# Fri3D_2020_00.net
KiCad netlist of a schematic drawn in Altium Designer
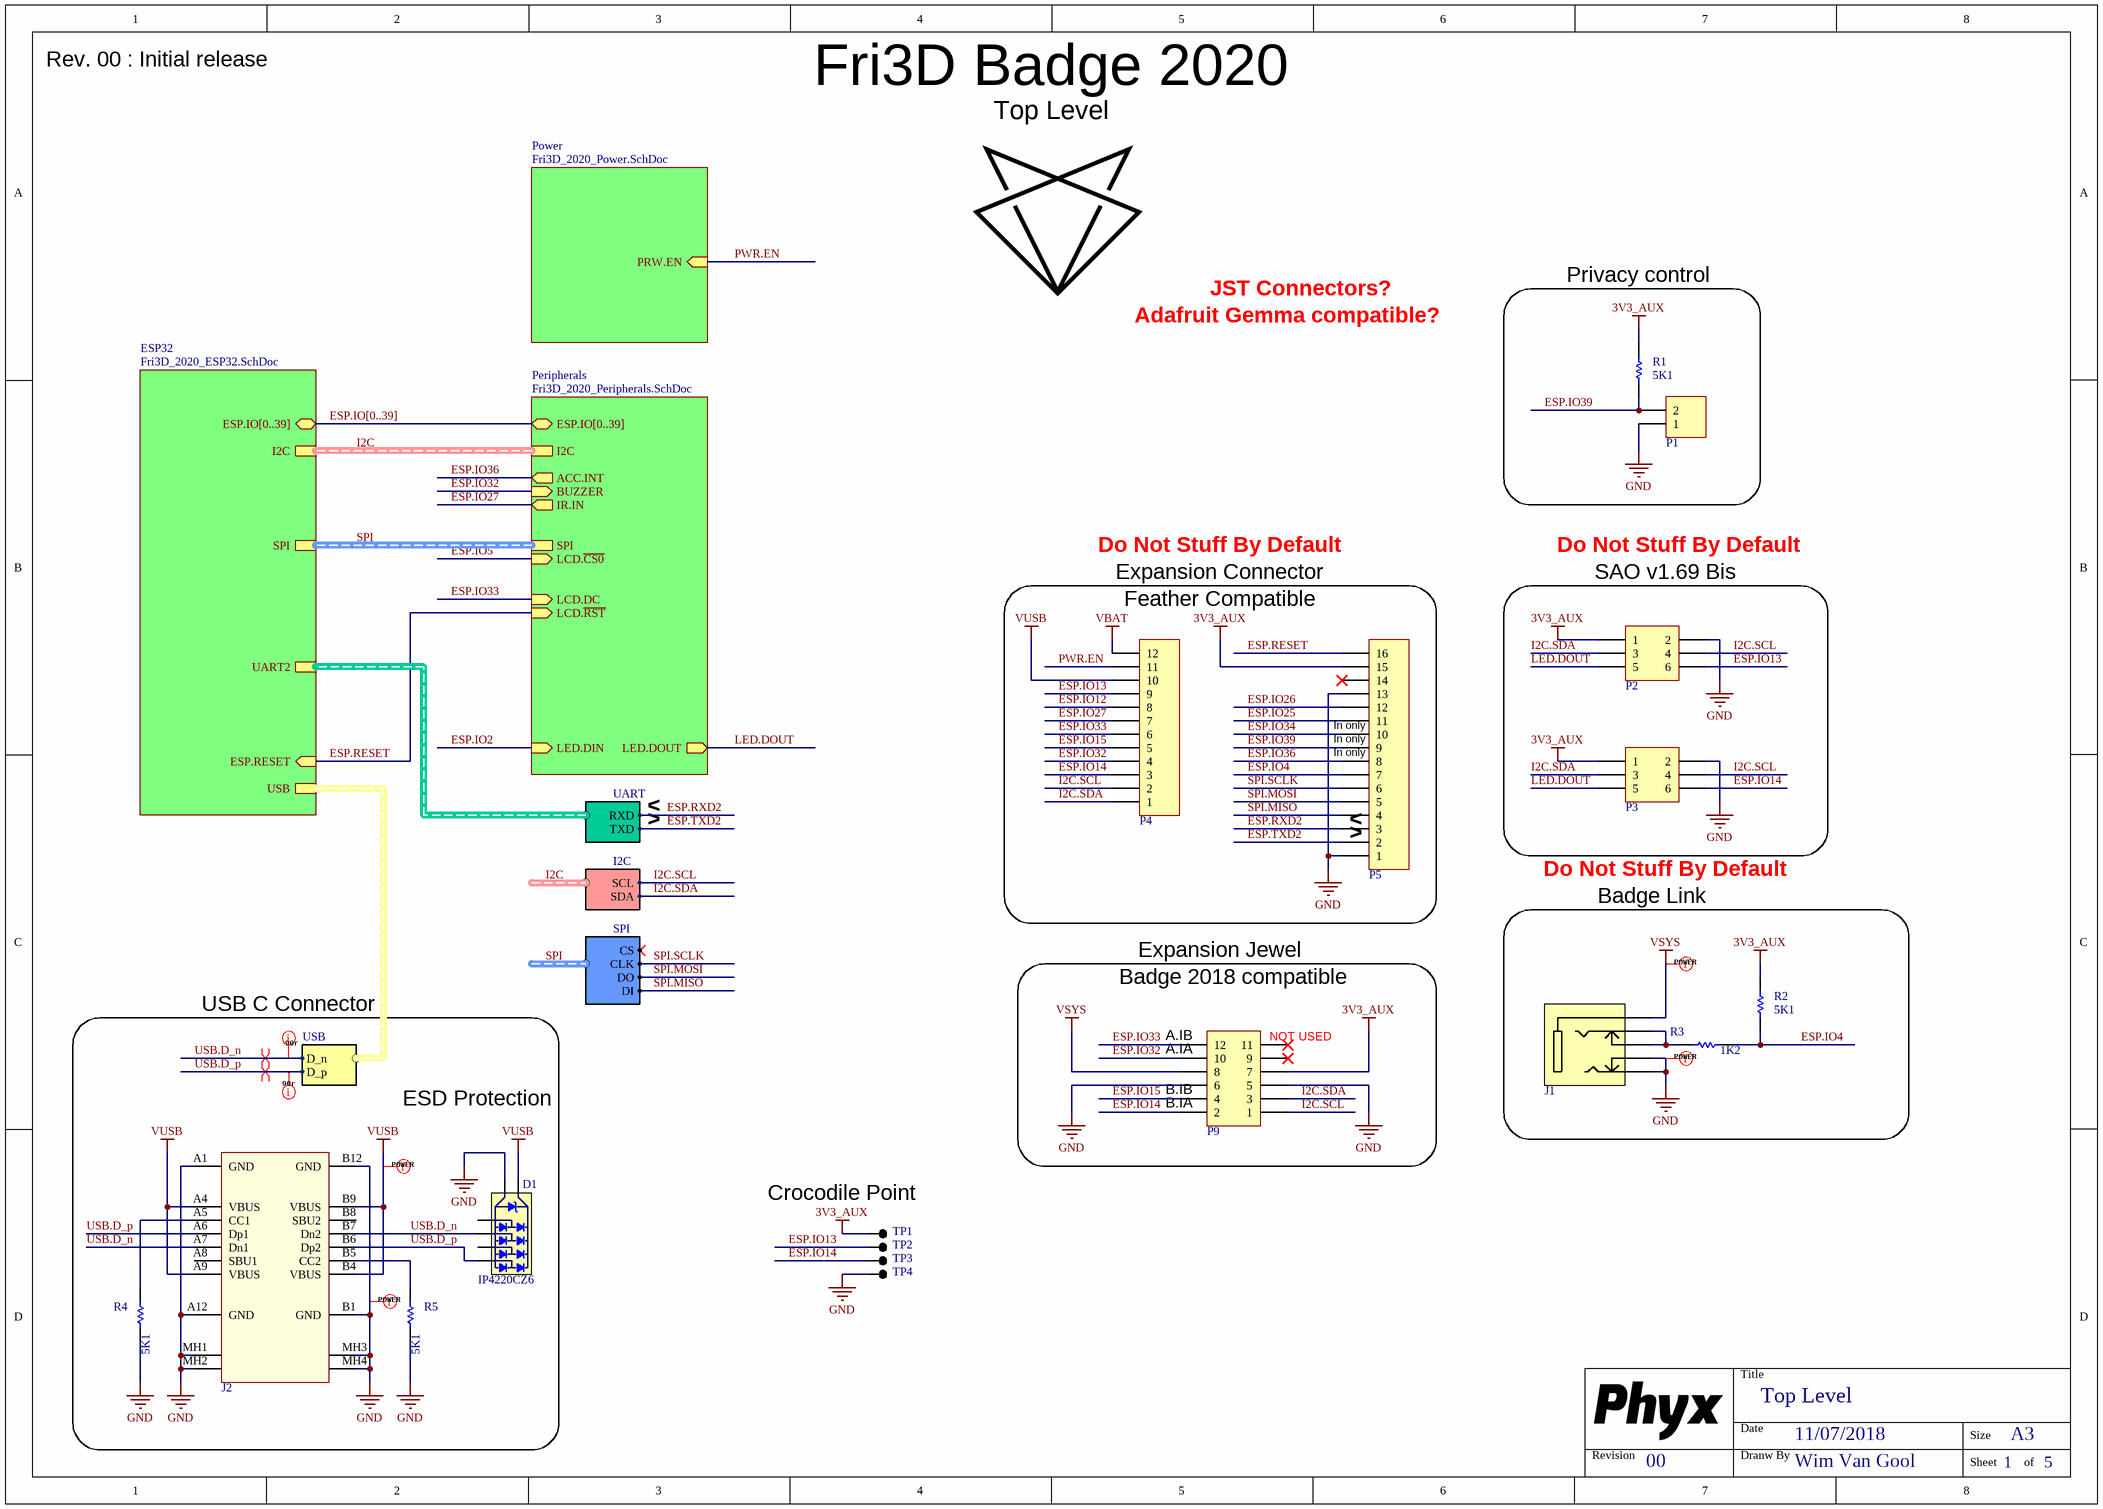
[diagram p0: Fri3D_2020_00.SchDoc]

(export (version "E")
  (design (tool "Eeschema 10.0.6"))
  (components
    (comp (ref "D1")
      (value "IP4220CZ6")
      (footprint "NXP_SOT457")
      (description "=Description")
      (fields (field (name "Comment") "TVS Diode Dual USB"))
      (libsource (lib "Phyx_Components") (part "NXP_IP4220CZ6"))
    )
    (comp (ref "J1")
      (value "3.5mm jack, dual switch, black, 3 contacts")
      (footprint "CUI_SJ1-3525NG")
      (description "=Description")
      (libsource (lib "Phyx_Components") (part "CUI_SJ1-3525NG"))
    )
    (comp (ref "J2")
      (value "USB 2.0 C Reversible Receptacle Horizontal")
      (footprint "HRO_TYPE-C-31-M-12")
      (libsource (lib "Phyx_Components") (part "USB_C_16_4"))
    )
    (comp (ref "P1")
      (value "Easy to solder connection")
      (footprint "SOLDER_SW_V_1MM")
      (libsource (lib "Phyx_Components") (part "Header 2"))
    )
    (comp (ref "P2")
      (value "Receptacle 3x2")
      (footprint "RCPT2X3")
      (libsource (lib "Phyx_Components") (part "Header 3X2"))
    )
    (comp (ref "P3")
      (value "Receptacle 3x2")
      (footprint "RCPT2X3")
      (libsource (lib "Phyx_Components") (part "Header 3X2"))
    )
    (comp (ref "P4")
      (value "Header 12")
      (footprint "HDR1X12")
      (libsource (lib "Phyx_Components") (part "Header 12"))
    )
    (comp (ref "P5")
      (value "Header 16")
      (footprint "HDR1X16")
      (libsource (lib "Phyx_Components") (part "Header 16"))
    )
    (comp (ref "P9")
      (value "Receptacle 6x2 SMD low profile")
      (footprint "WE_610312243021_POST")
      (libsource (lib "Phyx_Components") (part "Header 6X2"))
    )
    (comp (ref "R1")
      (value "5K1")
      (footprint "R0603_N")
      (fields (field (name "Comment") "RESISTOR"))
      (libsource (lib "Phyx_Components") (part "RESISTOR"))
    )
    (comp (ref "R2")
      (value "5K1")
      (footprint "R0603_N")
      (fields (field (name "Comment") "RESISTOR"))
      (libsource (lib "Phyx_Components") (part "RESISTOR"))
    )
    (comp (ref "R3")
      (value "1K2")
      (footprint "R0603_N")
      (fields (field (name "Comment") "RESISTOR"))
      (libsource (lib "Phyx_Components") (part "RESISTOR"))
    )
    (comp (ref "R4")
      (value "5K1")
      (footprint "R0603_N")
      (fields (field (name "Comment") "RESISTOR"))
      (libsource (lib "Phyx_Components") (part "RESISTOR"))
    )
    (comp (ref "R5")
      (value "5K1")
      (footprint "R0603_N")
      (fields (field (name "Comment") "RESISTOR"))
      (libsource (lib "Phyx_Components") (part "RESISTOR"))
    )
    (comp (ref "TP1")
      (value "TEST_PAD")
      (footprint "TP_0.8mm")
      (libsource (lib "Phyx_Components") (part "TEST_PAD"))
    )
    (comp (ref "TP2")
      (value "TEST_PAD")
      (footprint "TP_0.8mm")
      (libsource (lib "Phyx_Components") (part "TEST_PAD"))
    )
    (comp (ref "TP3")
      (value "TEST_PAD")
      (footprint "TP_0.8mm")
      (libsource (lib "Phyx_Components") (part "TEST_PAD"))
    )
    (comp (ref "TP4")
      (value "TEST_PAD")
      (footprint "TP_0.8mm")
      (libsource (lib "Phyx_Components") (part "TEST_PAD"))
    )
  )
  (nets
    (net (code "33") (name "/ESP.IO4") (class "Default")
      (node (ref "P5") (pin "7") (pinfunction "7_7") (pintype "passive"))
      (node (ref "R2") (pin "2") (pinfunction "2_2") (pintype "passive"))
      (node (ref "R3") (pin "1") (pinfunction "1_1") (pintype "passive"))
    )
    (net (code "35") (name "/ESP.IO12") (class "Default")
      (node (ref "P4") (pin "8") (pinfunction "8_8") (pintype "passive"))
    )
    (net (code "36") (name "/ESP.IO13") (class "Default")
      (node (ref "P2") (pin "6") (pinfunction "6_6") (pintype "passive"))
      (node (ref "P4") (pin "9") (pinfunction "9_9") (pintype "passive"))
      (node (ref "TP2") (pin "1") (pinfunction "1_1") (pintype "passive"))
    )
    (net (code "37") (name "/ESP.IO14") (class "Default")
      (node (ref "P3") (pin "6") (pinfunction "6_6") (pintype "passive"))
      (node (ref "P4") (pin "3") (pinfunction "3_3") (pintype "passive"))
      (node (ref "P9") (pin "2") (pinfunction "2_2") (pintype "passive"))
      (node (ref "TP3") (pin "1") (pinfunction "1_1") (pintype "passive"))
    )
    (net (code "38") (name "/ESP.IO15") (class "Default")
      (node (ref "P4") (pin "5") (pinfunction "5_5") (pintype "passive"))
      (node (ref "P9") (pin "4") (pinfunction "4_4") (pintype "passive"))
    )
    (net (code "39") (name "/ESP.IO25") (class "Default")
      (node (ref "P5") (pin "11") (pinfunction "11_11") (pintype "passive"))
    )
    (net (code "40") (name "/ESP.IO26") (class "Default")
      (node (ref "P5") (pin "12") (pinfunction "12_12") (pintype "passive"))
    )
    (net (code "41") (name "/ESP.IO27") (class "Default")
      (node (ref "P4") (pin "7") (pinfunction "7_7") (pintype "passive"))
    )
    (net (code "42") (name "/ESP.IO32") (class "Default")
      (node (ref "P4") (pin "4") (pinfunction "4_4") (pintype "passive"))
      (node (ref "P9") (pin "10") (pinfunction "10_10") (pintype "passive"))
    )
    (net (code "43") (name "/ESP.IO33") (class "Default")
      (node (ref "P4") (pin "6") (pinfunction "6_6") (pintype "passive"))
      (node (ref "P9") (pin "12") (pinfunction "12_12") (pintype "passive"))
    )
    (net (code "44") (name "/ESP.IO34") (class "Default")
      (node (ref "P5") (pin "10") (pinfunction "10_10") (pintype "passive"))
    )
    (net (code "45") (name "/ESP.IO36") (class "Default")
      (node (ref "P5") (pin "8") (pinfunction "8_8") (pintype "passive"))
    )
    (net (code "46") (name "/ESP.IO39") (class "Default")
      (node (ref "P1") (pin "2") (pinfunction "2_2") (pintype "passive"))
      (node (ref "P5") (pin "9") (pinfunction "9_9") (pintype "passive"))
      (node (ref "R1") (pin "2") (pinfunction "2_2") (pintype "passive"))
    )
    (net (code "48") (name "/ESP.RESET") (class "Default")
      (node (ref "P5") (pin "16") (pinfunction "16_16") (pintype "passive"))
    )
    (net (code "49") (name "/ESP.RXD2") (class "Default")
      (node (ref "P5") (pin "3") (pinfunction "3_3") (pintype "passive"))
    )
    (net (code "50") (name "/ESP.TXD2") (class "Default")
      (node (ref "P5") (pin "2") (pinfunction "2_2") (pintype "passive"))
    )
    (net (code "51") (name "/I2C.SCL") (class "Default")
      (node (ref "P2") (pin "4") (pinfunction "4_4") (pintype "passive"))
      (node (ref "P3") (pin "4") (pinfunction "4_4") (pintype "passive"))
      (node (ref "P4") (pin "2") (pinfunction "2_2") (pintype "passive"))
      (node (ref "P9") (pin "1") (pinfunction "1_1") (pintype "passive"))
    )
    (net (code "52") (name "/I2C.SDA") (class "Default")
      (node (ref "P2") (pin "3") (pinfunction "3_3") (pintype "passive"))
      (node (ref "P3") (pin "3") (pinfunction "3_3") (pintype "passive"))
      (node (ref "P4") (pin "1") (pinfunction "1_1") (pintype "passive"))
      (node (ref "P9") (pin "3") (pinfunction "3_3") (pintype "passive"))
    )
    (net (code "54") (name "/LED.DOUT") (class "Default")
      (node (ref "P2") (pin "5") (pinfunction "5_5") (pintype "passive"))
      (node (ref "P3") (pin "5") (pinfunction "5_5") (pintype "passive"))
    )
    (net (code "55") (name "/PWR.EN") (class "Default")
      (node (ref "P4") (pin "11") (pinfunction "11_11") (pintype "passive"))
    )
    (net (code "56") (name "/SPI.MISO") (class "Default")
      (node (ref "P5") (pin "4") (pinfunction "4_4") (pintype "passive"))
    )
    (net (code "57") (name "/SPI.MOSI") (class "Default")
      (node (ref "P5") (pin "5") (pinfunction "5_5") (pintype "passive"))
    )
    (net (code "58") (name "/SPI.SCLK") (class "Default")
      (node (ref "P5") (pin "6") (pinfunction "6_6") (pintype "passive"))
    )
    (net (code "60") (name "/USB.D_n") (class "Default")
      (node (ref "D1") (pin "1") (pinfunction "1_1") (pintype "passive"))
      (node (ref "J2") (pin "A7") (pinfunction "Dn1_A7") (pintype "passive"))
      (node (ref "J2") (pin "B7") (pinfunction "Dn2_B7") (pintype "passive"))
    )
    (net (code "61") (name "/USB.D_p") (class "Default")
      (node (ref "D1") (pin "6") (pinfunction "6_6") (pintype "passive"))
      (node (ref "J2") (pin "A6") (pinfunction "Dp1_A6") (pintype "passive"))
      (node (ref "J2") (pin "B6") (pinfunction "Dp2_B6") (pintype "passive"))
    )
    (net (code "66") (name "3V3_AUX") (class "Default")
      (node (ref "P2") (pin "1") (pinfunction "1_1") (pintype "passive"))
      (node (ref "P3") (pin "1") (pinfunction "1_1") (pintype "passive"))
      (node (ref "P5") (pin "15") (pinfunction "15_15") (pintype "passive"))
      (node (ref "P9") (pin "7") (pinfunction "7_7") (pintype "passive"))
      (node (ref "R1") (pin "1") (pinfunction "1_1") (pintype "passive"))
      (node (ref "R2") (pin "1") (pinfunction "1_1") (pintype "passive"))
      (node (ref "TP1") (pin "1") (pinfunction "1_1") (pintype "passive"))
    )
    (net (code "67") (name "GND") (class "Default")
      (node (ref "D1") (pin "2") (pinfunction "GND_2") (pintype "passive"))
      (node (ref "J1") (pin "2") (pinfunction "Tip_2") (pintype "passive"))
      (node (ref "J1") (pin "4") (pinfunction "4_4") (pintype "passive"))
      (node (ref "J2") (pin "A1") (pinfunction "GND_A1") (pintype "passive"))
      (node (ref "J2") (pin "A12") (pinfunction "GND_A12") (pintype "passive"))
      (node (ref "J2") (pin "B1") (pinfunction "GND_B1") (pintype "passive"))
      (node (ref "J2") (pin "B12") (pinfunction "GND_B12") (pintype "passive"))
      (node (ref "J2") (pin "MH1") (pinfunction "Tab_MH1") (pintype "passive"))
      (node (ref "J2") (pin "MH2") (pinfunction "Tab_MH2") (pintype "passive"))
      (node (ref "J2") (pin "MH3") (pinfunction "Tab_MH3") (pintype "passive"))
      (node (ref "J2") (pin "MH4") (pinfunction "Tab_MH4") (pintype "passive"))
      (node (ref "P1") (pin "1") (pinfunction "1_1") (pintype "passive"))
      (node (ref "P2") (pin "2") (pinfunction "2_2") (pintype "passive"))
      (node (ref "P3") (pin "2") (pinfunction "2_2") (pintype "passive"))
      (node (ref "P5") (pin "1") (pinfunction "1_1") (pintype "passive"))
      (node (ref "P5") (pin "13") (pinfunction "13_13") (pintype "passive"))
      (node (ref "P9") (pin "5") (pinfunction "5_5") (pintype "passive"))
      (node (ref "P9") (pin "6") (pinfunction "6_6") (pintype "passive"))
      (node (ref "R4") (pin "2") (pinfunction "2_2") (pintype "passive"))
      (node (ref "R5") (pin "2") (pinfunction "2_2") (pintype "passive"))
      (node (ref "TP4") (pin "1") (pinfunction "1_1") (pintype "passive"))
    )
    (net (code "68") (name "Net-(J1-Ring)") (class "Default")
      (node (ref "J1") (pin "3") (pinfunction "Ring_3") (pintype "passive"))
      (node (ref "J1") (pin "5") (pinfunction "5_5") (pintype "passive"))
      (node (ref "R3") (pin "2") (pinfunction "2_2") (pintype "passive"))
    )
    (net (code "69") (name "Net-(J2-CC1)") (class "Default")
      (node (ref "J2") (pin "A5") (pinfunction "CC1_A5") (pintype "passive"))
      (node (ref "R4") (pin "1") (pinfunction "1_1") (pintype "passive"))
    )
    (net (code "70") (name "Net-(J2-CC2)") (class "Default")
      (node (ref "J2") (pin "B5") (pinfunction "CC2_B5") (pintype "passive"))
      (node (ref "R5") (pin "1") (pinfunction "1_1") (pintype "passive"))
    )
    (net (code "71") (name "VBAT") (class "Default")
      (node (ref "P4") (pin "12") (pinfunction "12_12") (pintype "passive"))
    )
    (net (code "72") (name "VSYS") (class "Default")
      (node (ref "J1") (pin "1") (pinfunction "Sleeve_1") (pintype "passive"))
      (node (ref "P9") (pin "8") (pinfunction "8_8") (pintype "passive"))
    )
    (net (code "73") (name "VUSB") (class "Default")
      (node (ref "D1") (pin "5") (pinfunction "VBus_5") (pintype "passive"))
      (node (ref "J2") (pin "A4") (pinfunction "VBUS_A4") (pintype "passive"))
      (node (ref "J2") (pin "A9") (pinfunction "VBUS_A9") (pintype "passive"))
      (node (ref "J2") (pin "B4") (pinfunction "VBUS_B4") (pintype "passive"))
      (node (ref "J2") (pin "B9") (pinfunction "VBUS_B9") (pintype "passive"))
      (node (ref "P4") (pin "10") (pinfunction "10_10") (pintype "passive"))
    )
    (net (code "74") (name "unconnected-(D1-Pad3)") (class "Default")
      (node (ref "D1") (pin "3") (pinfunction "3_3") (pintype "passive"))
    )
    (net (code "75") (name "unconnected-(D1-Pad4)") (class "Default")
      (node (ref "D1") (pin "4") (pinfunction "4_4") (pintype "passive"))
    )
    (net (code "76") (name "unconnected-(J2-SBU1-PadA8)") (class "Default")
      (node (ref "J2") (pin "A8") (pinfunction "SBU1_A8") (pintype "passive"))
    )
    (net (code "77") (name "unconnected-(J2-SBU2-PadB8)") (class "Default")
      (node (ref "J2") (pin "B8") (pinfunction "SBU2_B8") (pintype "passive"))
    )
    (net (code "78") (name "unconnected-(P5-Pad14)") (class "Default")
      (node (ref "P5") (pin "14") (pinfunction "14_14") (pintype "passive+no_connect"))
    )
    (net (code "79") (name "unconnected-(P9-Pad9)") (class "Default")
      (node (ref "P9") (pin "9") (pinfunction "9_9") (pintype "passive+no_connect"))
    )
    (net (code "80") (name "unconnected-(P9-Pad11)") (class "Default")
      (node (ref "P9") (pin "11") (pinfunction "11_11") (pintype "passive+no_connect"))
    )
  )
)
